# TC_masterProto_Pi.net
KiCad netlist of a schematic drawn in EAGLE
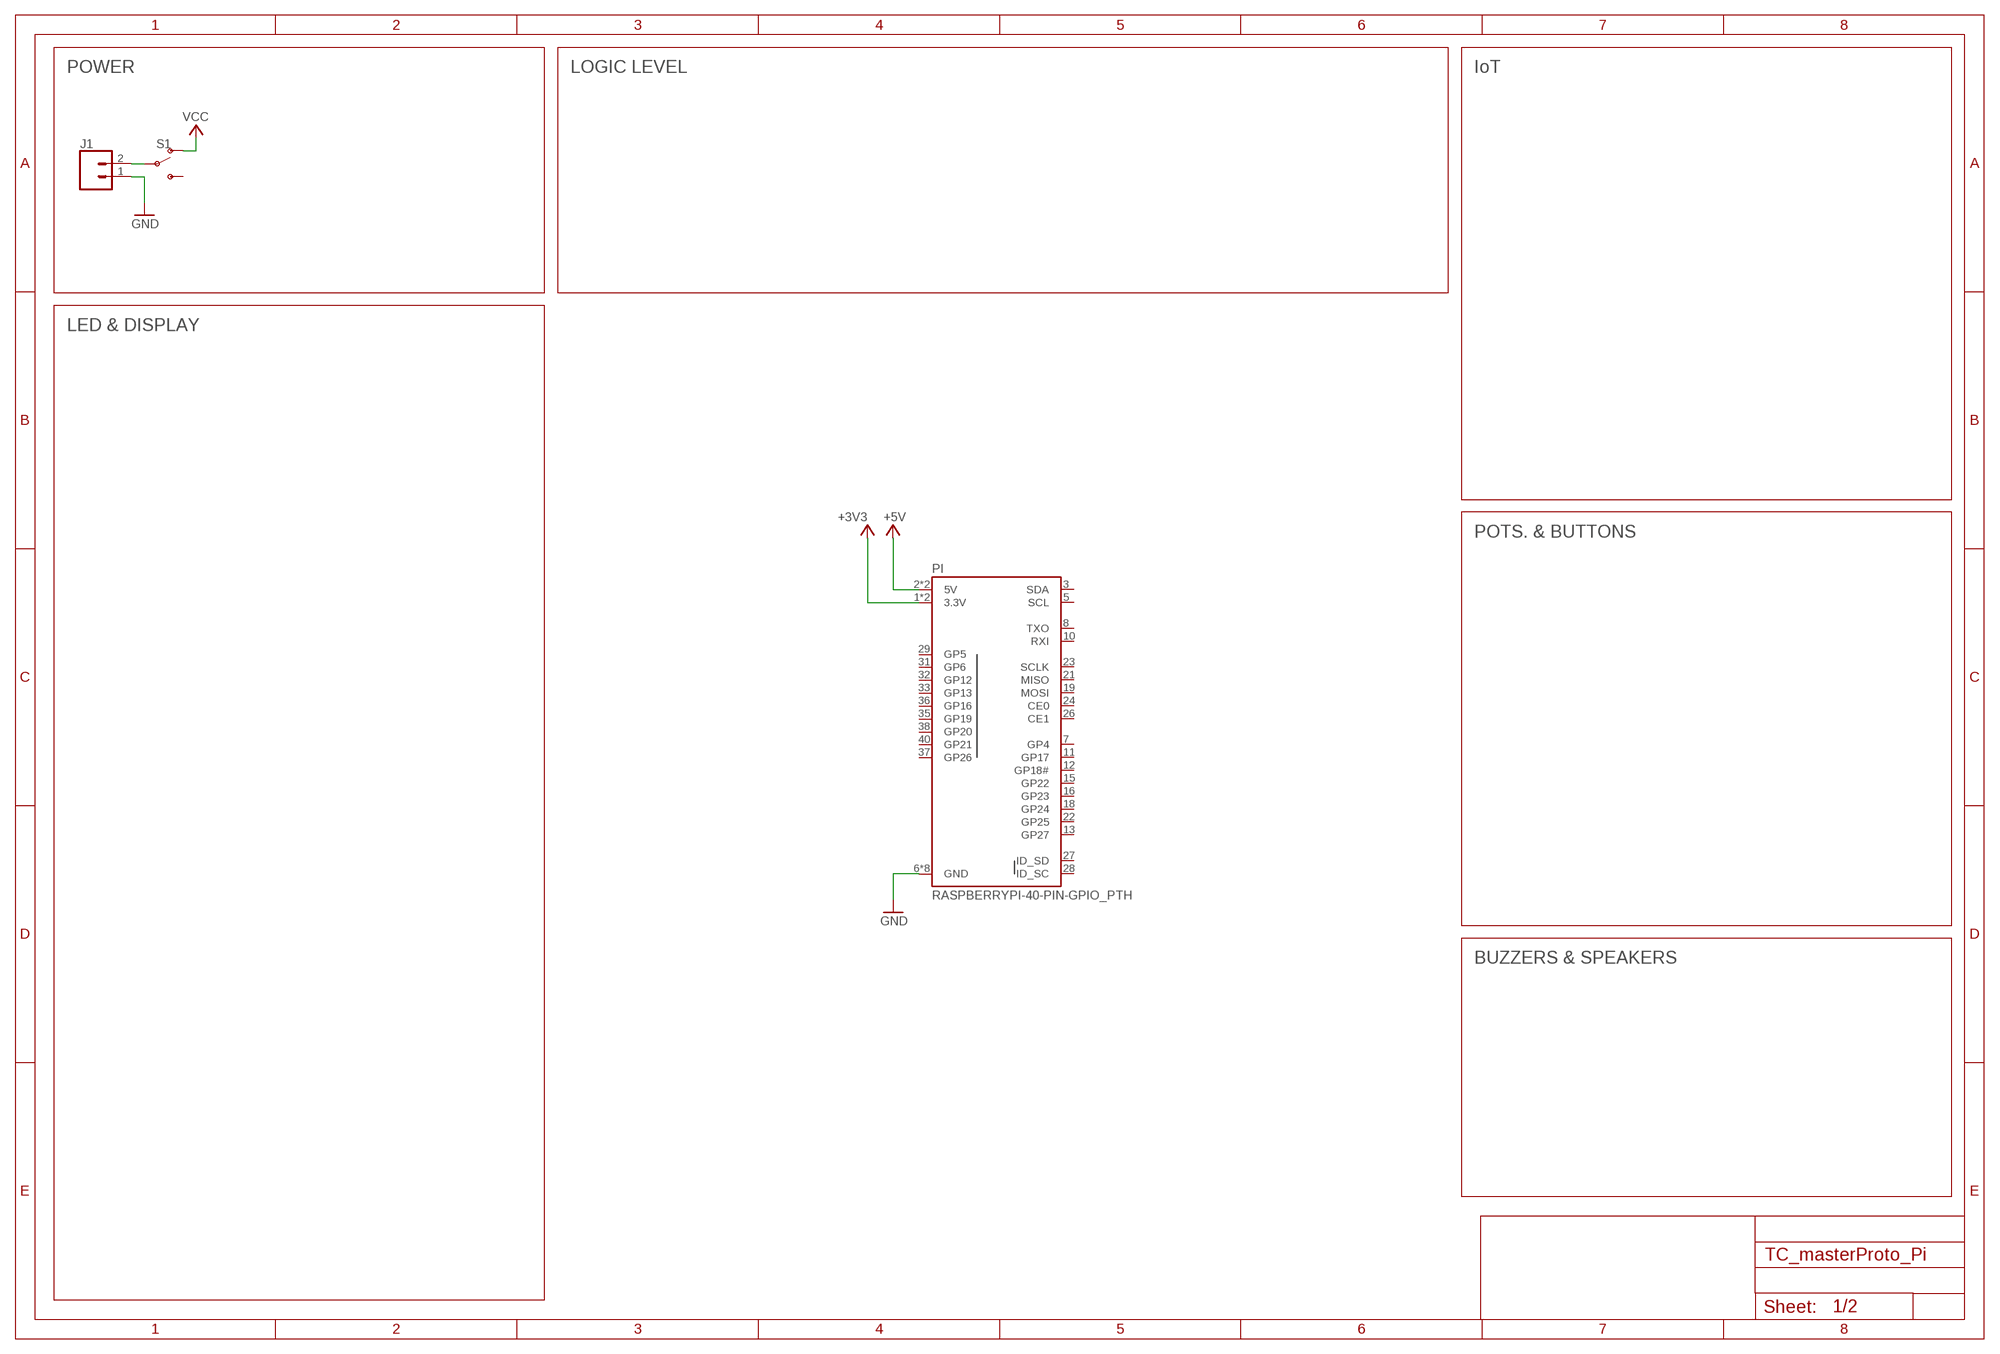
[diagram p0: schematic, sheet 1]
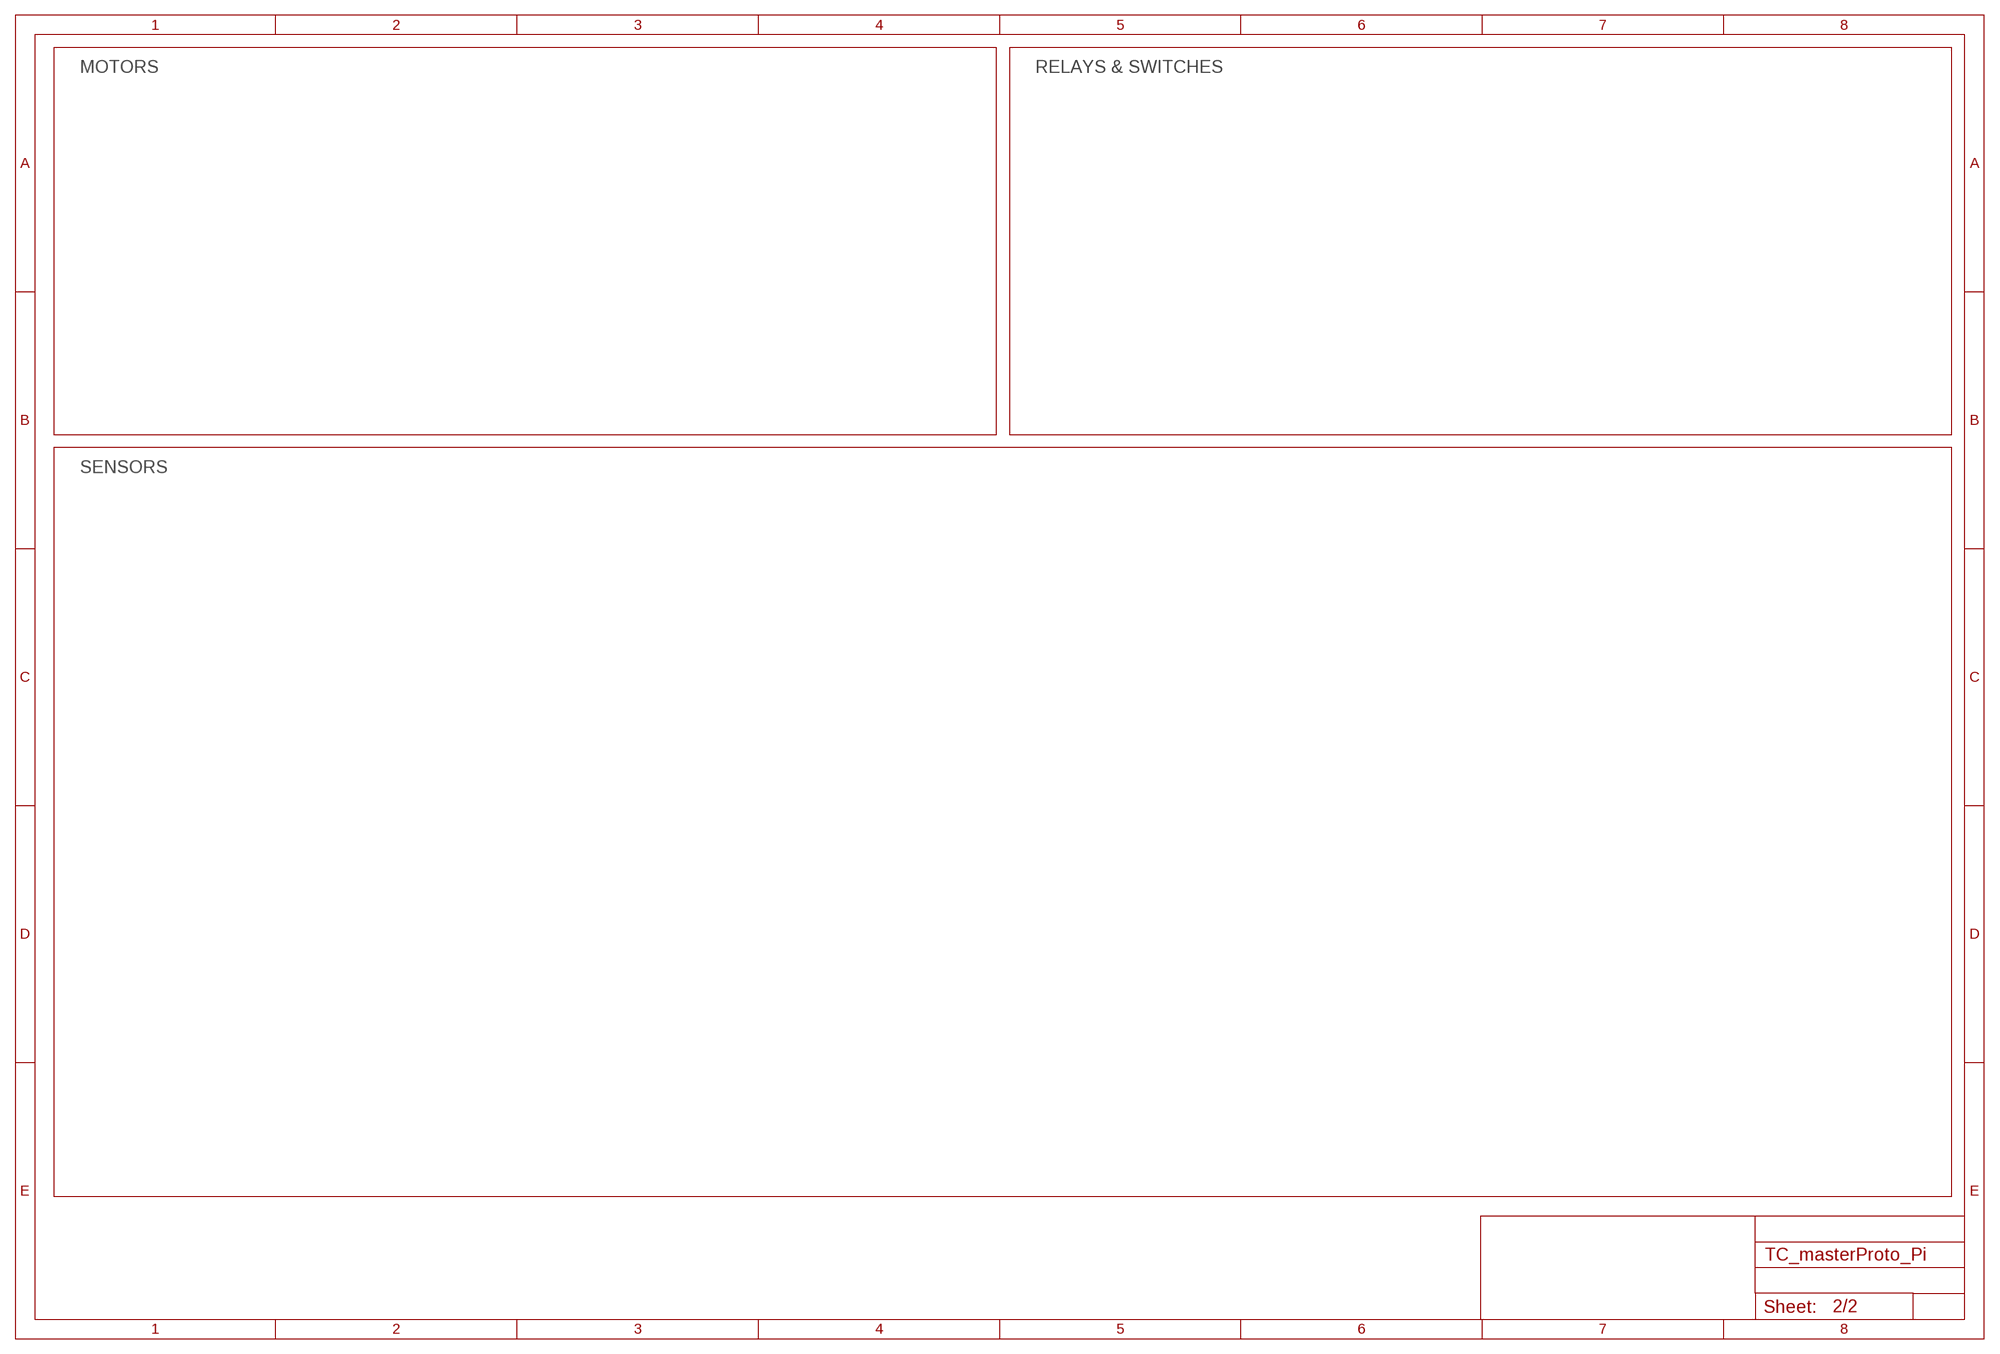
[diagram p1: schematic, sheet 2]

(export (version "E")
  (design (tool "Eeschema 10.0.6"))
  (components
    (comp (ref "J1")
      (value "CONN_023.5MM_LOCK")
      (footprint "eagle-import:SCREWTERMINAL-3.5MM-2_LOCK")
      (libsource (lib "eagle-import") (part "CONN_023.5MM_LOCK"))
    )
    (comp (ref "PI")
      (value "RASPBERRYPI-40-PIN-GPIO_PTH")
      (footprint "eagle-import:2X20_SHROUDED")
      (libsource (lib "eagle-import") (part "RASPBERRYPI-40-PIN-GPIO_PTH"))
    )
    (comp (ref "S1")
      (value "SWITCH-SPDT-PTH-11.6X4.0MM-LOCK")
      (footprint "eagle-import:SWITCH_SPDT_PTH_11.6X4.0MM_LOCK")
      (libsource (lib "eagle-import") (part "SWITCH-SPDT-PTH-11.6X4.0MM-LOCK"))
    )
  )
  (nets
    (net (code "1") (name "+3V3") (class "Default")
      (node (ref "PI") (pin "1") (pinfunction "3.3V_1") (pintype "power_in"))
      (node (ref "PI") (pin "17") (pinfunction "3.3V_17") (pintype "power_in"))
    )
    (net (code "2") (name "+5V") (class "Default")
      (node (ref "PI") (pin "2") (pinfunction "5V_2") (pintype "power_in"))
      (node (ref "PI") (pin "4") (pinfunction "5V_4") (pintype "power_in"))
    )
    (net (code "3") (name "GND") (class "Default")
      (node (ref "J1") (pin "1") (pinfunction "1_1") (pintype "passive"))
      (node (ref "PI") (pin "14") (pinfunction "GND_14") (pintype "power_in"))
      (node (ref "PI") (pin "20") (pinfunction "GND_20") (pintype "power_in"))
      (node (ref "PI") (pin "25") (pinfunction "GND_25") (pintype "power_in"))
      (node (ref "PI") (pin "30") (pinfunction "GND_30") (pintype "power_in"))
      (node (ref "PI") (pin "34") (pinfunction "GND_34") (pintype "power_in"))
      (node (ref "PI") (pin "39") (pinfunction "GND_39") (pintype "power_in"))
      (node (ref "PI") (pin "6") (pinfunction "GND_6") (pintype "power_in"))
      (node (ref "PI") (pin "9") (pinfunction "GND_9") (pintype "power_in"))
    )
    (net (code "4") (name "Net-(S1-P)") (class "Default")
      (node (ref "J1") (pin "2") (pinfunction "2_2") (pintype "passive"))
      (node (ref "S1") (pin "2") (pinfunction "P_2") (pintype "passive"))
    )
    (net (code "5") (name "VCC") (class "Default")
      (node (ref "S1") (pin "1") (pinfunction "O_1") (pintype "passive"))
    )
    (net (code "6") (name "unconnected-(PI-CE0-Pad24)") (class "Default")
      (node (ref "PI") (pin "24") (pinfunction "CE0_24") (pintype "output"))
    )
    (net (code "7") (name "unconnected-(PI-CE1-Pad26)") (class "Default")
      (node (ref "PI") (pin "26") (pinfunction "CE1_26") (pintype "output"))
    )
    (net (code "8") (name "unconnected-(PI-GP4-Pad7)") (class "Default")
      (node (ref "PI") (pin "7") (pinfunction "GP4_7") (pintype "bidirectional"))
    )
    (net (code "9") (name "unconnected-(PI-GP5-Pad29)") (class "Default")
      (node (ref "PI") (pin "29") (pinfunction "GP5_29") (pintype "bidirectional"))
    )
    (net (code "10") (name "unconnected-(PI-GP6-Pad31)") (class "Default")
      (node (ref "PI") (pin "31") (pinfunction "GP6_31") (pintype "bidirectional"))
    )
    (net (code "11") (name "unconnected-(PI-GP12-Pad32)") (class "Default")
      (node (ref "PI") (pin "32") (pinfunction "GP12_32") (pintype "bidirectional"))
    )
    (net (code "12") (name "unconnected-(PI-GP13-Pad33)") (class "Default")
      (node (ref "PI") (pin "33") (pinfunction "GP13_33") (pintype "bidirectional"))
    )
    (net (code "13") (name "unconnected-(PI-GP16-Pad36)") (class "Default")
      (node (ref "PI") (pin "36") (pinfunction "GP16_36") (pintype "bidirectional"))
    )
    (net (code "14") (name "unconnected-(PI-GP17-Pad11)") (class "Default")
      (node (ref "PI") (pin "11") (pinfunction "GP17_11") (pintype "bidirectional"))
    )
    (net (code "15") (name "unconnected-(PI-GP18#-Pad12)") (class "Default")
      (node (ref "PI") (pin "12") (pinfunction "GP18#_12") (pintype "bidirectional"))
    )
    (net (code "16") (name "unconnected-(PI-GP19-Pad35)") (class "Default")
      (node (ref "PI") (pin "35") (pinfunction "GP19_35") (pintype "bidirectional"))
    )
    (net (code "17") (name "unconnected-(PI-GP20-Pad38)") (class "Default")
      (node (ref "PI") (pin "38") (pinfunction "GP20_38") (pintype "bidirectional"))
    )
    (net (code "18") (name "unconnected-(PI-GP21-Pad40)") (class "Default")
      (node (ref "PI") (pin "40") (pinfunction "GP21_40") (pintype "bidirectional"))
    )
    (net (code "19") (name "unconnected-(PI-GP22-Pad15)") (class "Default")
      (node (ref "PI") (pin "15") (pinfunction "GP22_15") (pintype "bidirectional"))
    )
    (net (code "20") (name "unconnected-(PI-GP23-Pad16)") (class "Default")
      (node (ref "PI") (pin "16") (pinfunction "GP23_16") (pintype "bidirectional"))
    )
    (net (code "21") (name "unconnected-(PI-GP24-Pad18)") (class "Default")
      (node (ref "PI") (pin "18") (pinfunction "GP24_18") (pintype "bidirectional"))
    )
    (net (code "22") (name "unconnected-(PI-GP25-Pad22)") (class "Default")
      (node (ref "PI") (pin "22") (pinfunction "GP25_22") (pintype "bidirectional"))
    )
    (net (code "23") (name "unconnected-(PI-GP26-Pad37)") (class "Default")
      (node (ref "PI") (pin "37") (pinfunction "GP26_37") (pintype "bidirectional"))
    )
    (net (code "24") (name "unconnected-(PI-GP27-Pad13)") (class "Default")
      (node (ref "PI") (pin "13") (pinfunction "GP27_13") (pintype "bidirectional"))
    )
    (net (code "25") (name "unconnected-(PI-ID_SC-Pad28)") (class "Default")
      (node (ref "PI") (pin "28") (pinfunction "ID_SC_28") (pintype "bidirectional"))
    )
    (net (code "26") (name "unconnected-(PI-ID_SD-Pad27)") (class "Default")
      (node (ref "PI") (pin "27") (pinfunction "ID_SD_27") (pintype "bidirectional"))
    )
    (net (code "27") (name "unconnected-(PI-MISO-Pad21)") (class "Default")
      (node (ref "PI") (pin "21") (pinfunction "MISO_21") (pintype "input"))
    )
    (net (code "28") (name "unconnected-(PI-MOSI-Pad19)") (class "Default")
      (node (ref "PI") (pin "19") (pinfunction "MOSI_19") (pintype "output"))
    )
    (net (code "29") (name "unconnected-(PI-RXI-Pad10)") (class "Default")
      (node (ref "PI") (pin "10") (pinfunction "RXI_10") (pintype "input"))
    )
    (net (code "30") (name "unconnected-(PI-SCL-Pad5)") (class "Default")
      (node (ref "PI") (pin "5") (pinfunction "SCL_5") (pintype "bidirectional"))
    )
    (net (code "31") (name "unconnected-(PI-SCLK-Pad23)") (class "Default")
      (node (ref "PI") (pin "23") (pinfunction "SCLK_23") (pintype "output"))
    )
    (net (code "32") (name "unconnected-(PI-SDA-Pad3)") (class "Default")
      (node (ref "PI") (pin "3") (pinfunction "SDA_3") (pintype "bidirectional"))
    )
    (net (code "33") (name "unconnected-(PI-TXO-Pad8)") (class "Default")
      (node (ref "PI") (pin "8") (pinfunction "TXO_8") (pintype "output"))
    )
    (net (code "34") (name "unconnected-(S1-S-Pad3)") (class "Default")
      (node (ref "S1") (pin "3") (pinfunction "S_3") (pintype "passive"))
    )
  )
)
